# TSOC-ENCORE3.net
KiCad netlist of a schematic drawn in EAGLE
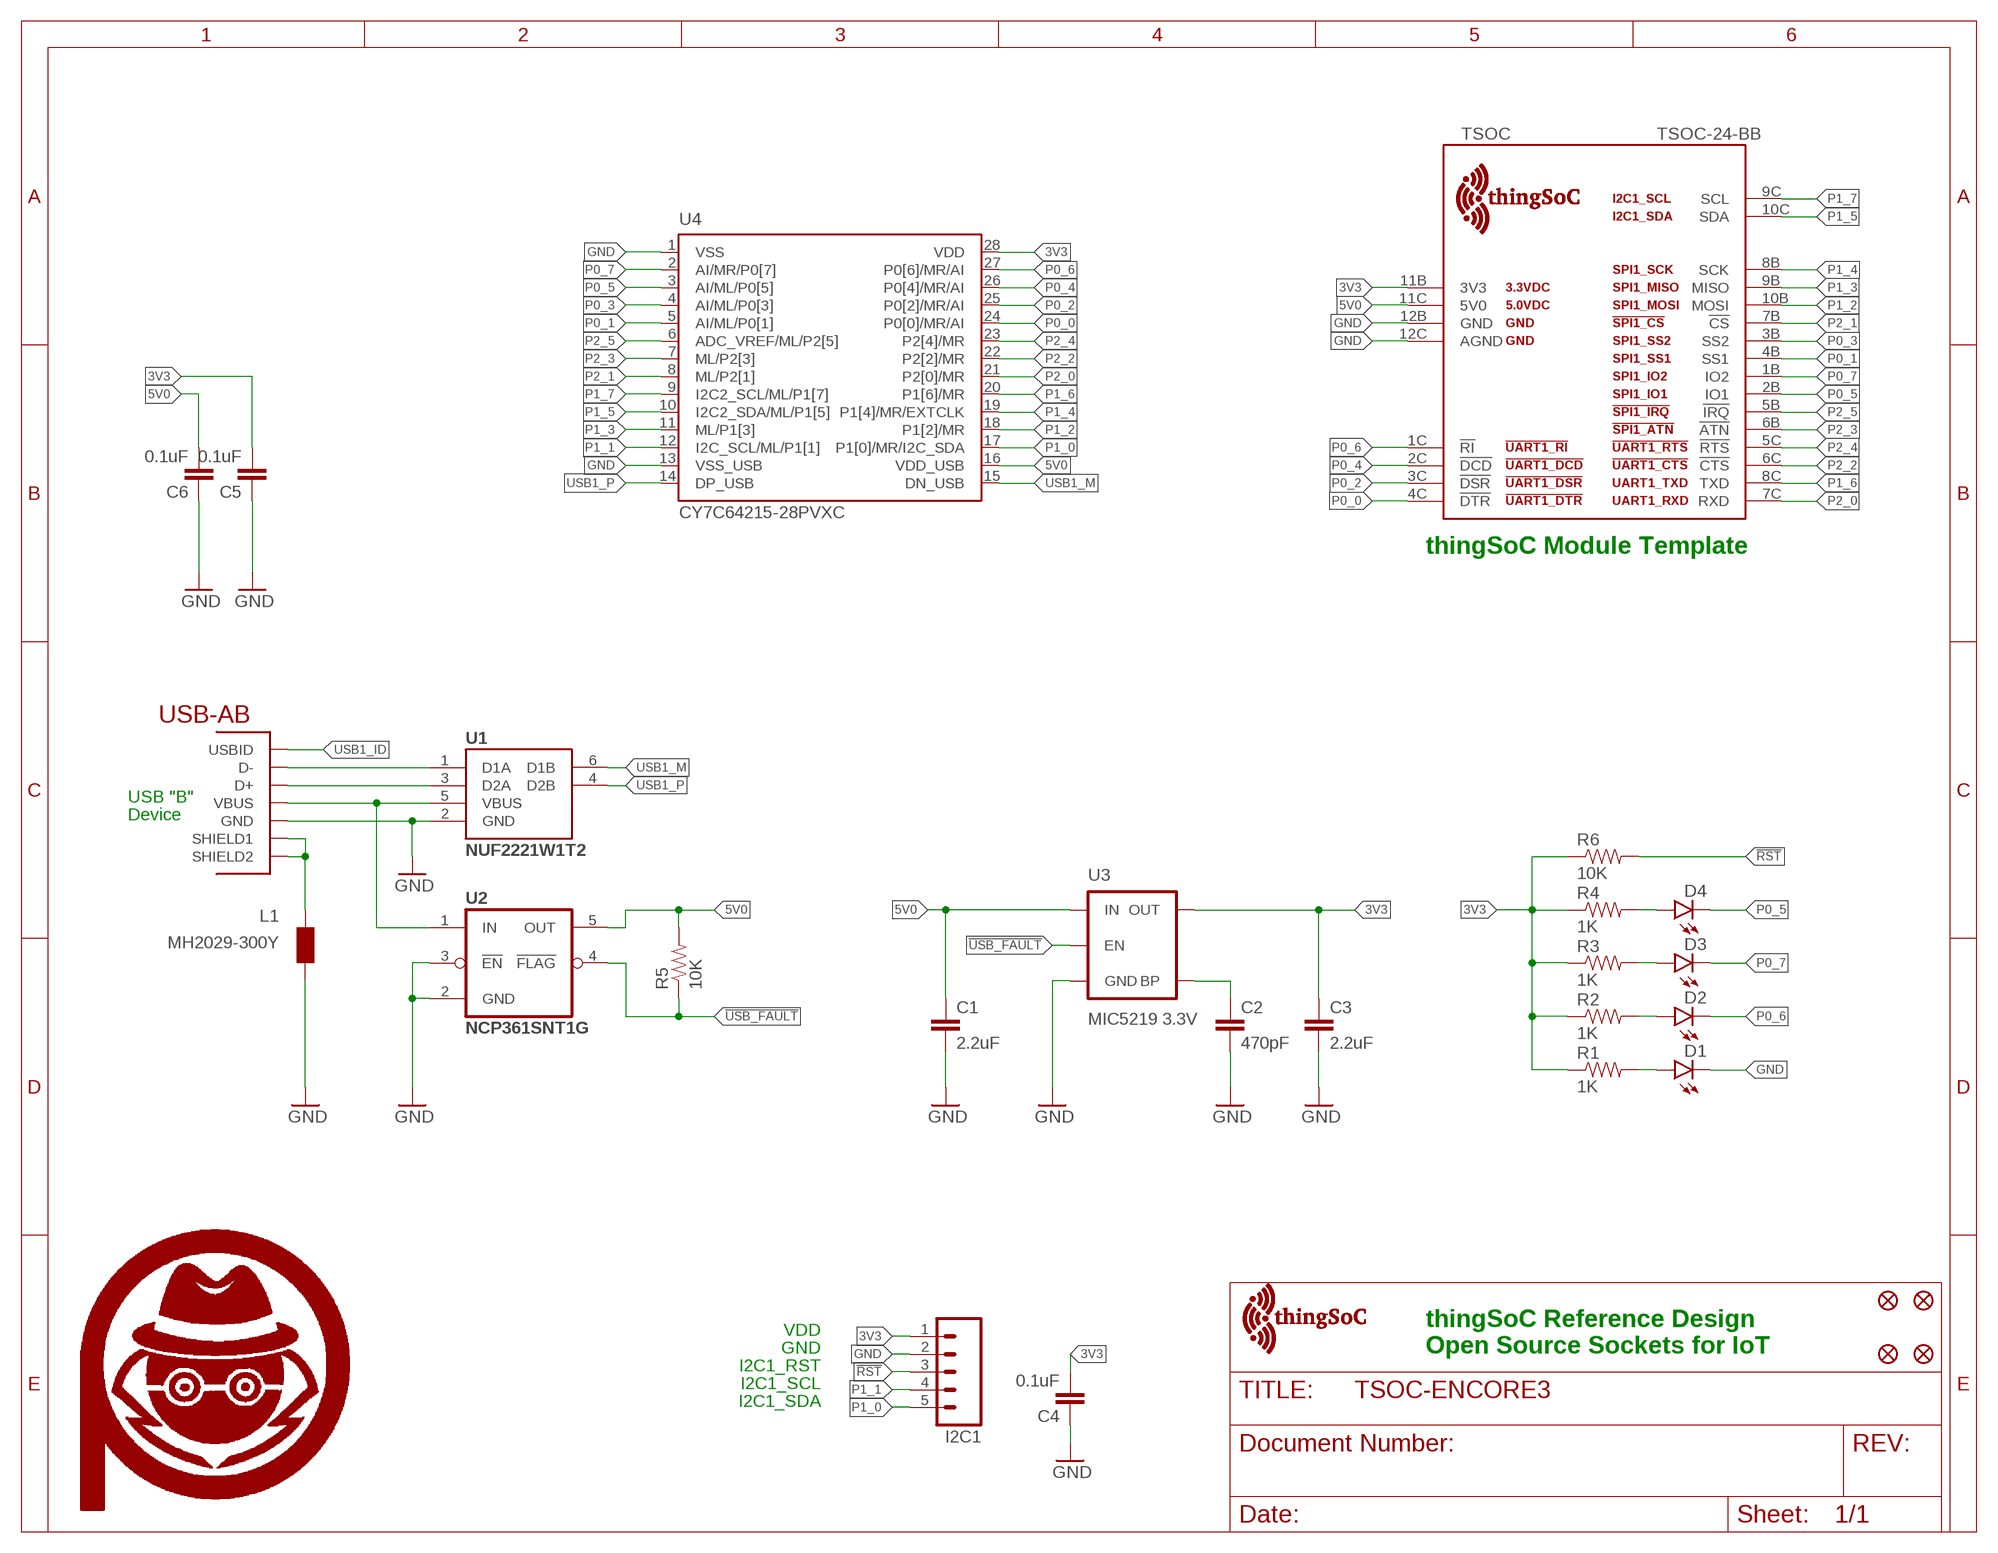
[diagram p0: schematic, sheet 1]

(export (version "E")
  (design (tool "Eeschema 10.0.6"))
  (components
    (comp (ref "C1")
      (value "2.2uF")
      (footprint "eagle-import:0603-CAP")
      (libsource (lib "eagle-import") (part "CAP0603-CAP"))
    )
    (comp (ref "C2")
      (value "470pF")
      (footprint "eagle-import:0603-CAP")
      (libsource (lib "eagle-import") (part "CAP0603-CAP"))
    )
    (comp (ref "C3")
      (value "2.2uF")
      (footprint "eagle-import:0603-CAP")
      (libsource (lib "eagle-import") (part "CAP0603-CAP"))
    )
    (comp (ref "C4")
      (value "0.1uF")
      (footprint "eagle-import:0603-CAP")
      (libsource (lib "eagle-import") (part "CAP0603-CAP"))
    )
    (comp (ref "C5")
      (value "0.1uF")
      (footprint "eagle-import:0603-CAP")
      (libsource (lib "eagle-import") (part "CAP0603-CAP"))
    )
    (comp (ref "C6")
      (value "0.1uF")
      (footprint "eagle-import:0603-CAP")
      (libsource (lib "eagle-import") (part "CAP0603-CAP"))
    )
    (comp (ref "D1")
      (value "LED0603")
      (footprint "eagle-import:LED-0603")
      (libsource (lib "eagle-import") (part "LED0603"))
    )
    (comp (ref "D2")
      (value "LED0603")
      (footprint "eagle-import:LED-0603")
      (libsource (lib "eagle-import") (part "LED0603"))
    )
    (comp (ref "D3")
      (value "LED0603")
      (footprint "eagle-import:LED-0603")
      (libsource (lib "eagle-import") (part "LED0603"))
    )
    (comp (ref "D4")
      (value "LED0603")
      (footprint "eagle-import:LED-0603")
      (libsource (lib "eagle-import") (part "LED0603"))
    )
    (comp (ref "FID1")
      (value "FIDUCIAL1.5X3")
      (footprint "eagle-import:FIDUCIAL-1.5X3")
      (libsource (lib "eagle-import") (part "FIDUCIAL1.5X3"))
    )
    (comp (ref "FID2")
      (value "FIDUCIAL1.5X3")
      (footprint "eagle-import:FIDUCIAL-1.5X3")
      (libsource (lib "eagle-import") (part "FIDUCIAL1.5X3"))
    )
    (comp (ref "FID3")
      (value "FIDUCIAL1.5X3")
      (footprint "eagle-import:FIDUCIAL-1.5X3")
      (libsource (lib "eagle-import") (part "FIDUCIAL1.5X3"))
    )
    (comp (ref "FID4")
      (value "FIDUCIAL1.5X3")
      (footprint "eagle-import:FIDUCIAL-1.5X3")
      (libsource (lib "eagle-import") (part "FIDUCIAL1.5X3"))
    )
    (comp (ref "I2C1")
      (value "M05PTH")
      (footprint "eagle-import:1X05")
      (libsource (lib "eagle-import") (part "M05PTH"))
    )
    (comp (ref "L1")
      (value "MH2029-300Y")
      (footprint "eagle-import:0805")
      (libsource (lib "eagle-import") (part "WE-CBF_0805"))
    )
    (comp (ref "R1")
      (value "1K")
      (footprint "eagle-import:0603-RES")
      (libsource (lib "eagle-import") (part "RESISTOR0603-RES"))
    )
    (comp (ref "R2")
      (value "1K")
      (footprint "eagle-import:0603-RES")
      (libsource (lib "eagle-import") (part "RESISTOR0603-RES"))
    )
    (comp (ref "R3")
      (value "1K")
      (footprint "eagle-import:0603-RES")
      (libsource (lib "eagle-import") (part "RESISTOR0603-RES"))
    )
    (comp (ref "R4")
      (value "1K")
      (footprint "eagle-import:0603-RES")
      (libsource (lib "eagle-import") (part "RESISTOR0603-RES"))
    )
    (comp (ref "R5")
      (value "10K")
      (footprint "eagle-import:0603-RES")
      (libsource (lib "eagle-import") (part "RESISTOR0603-RES"))
    )
    (comp (ref "R6")
      (value "10K")
      (footprint "eagle-import:0603-RES")
      (libsource (lib "eagle-import") (part "RESISTOR0603-RES"))
    )
    (comp (ref "TSOC")
      (value "TSOC-24-BB")
      (footprint "eagle-import:TSOC-BB-S24")
      (libsource (lib "eagle-import") (part "TSOC-24-BB"))
    )
    (comp (ref "U$1")
      (value "PA_LOGO_SYMNULL")
      (footprint "eagle-import:NULL_SYM")
      (libsource (lib "eagle-import") (part "PA_LOGO_SYMNULL"))
    )
    (comp (ref "U$2")
      (value "TSOC-LOGO-MED")
      (footprint "eagle-import:TSOC-LOGO-MED")
      (libsource (lib "eagle-import") (part "TSOC-LOGO-MED"))
    )
    (comp (ref "U$3")
      (value "TSOC-LOGO-MED")
      (footprint "eagle-import:TSOC-LOGO-MED")
      (libsource (lib "eagle-import") (part "TSOC-LOGO-MED"))
    )
    (comp (ref "U1")
      (value "NUF2221W1T2")
      (footprint "eagle-import:SOT-363")
      (libsource (lib "eagle-import") (part "NUF2221W1T2"))
    )
    (comp (ref "U2")
      (value "NCP361SNT1G")
      (footprint "eagle-import:SOP95P275X110-5N")
      (libsource (lib "eagle-import") (part "NCP361SNT1G"))
    )
    (comp (ref "U3")
      (value "MIC5219 3.3V")
      (footprint "eagle-import:SOT23-5")
      (libsource (lib "eagle-import") (part "V_REG_MIC52193.3V"))
    )
    (comp (ref "U4")
      (value "CY7C64215-28PVXC")
      (footprint "eagle-import:SSOP28")
      (libsource (lib "eagle-import") (part "CY7C64215-28PVXC"))
    )
    (comp (ref "USB1")
      (value "USB_AB")
      (footprint "eagle-import:USB-AB-MICRO-SMD")
      (libsource (lib "eagle-import") (part "USB_AB"))
    )
  )
  (nets
    (net (code "1") (name "/~{RST}") (class "Default")
      (node (ref "I2C1") (pin "3") (pinfunction "3_3") (pintype "passive"))
      (node (ref "R6") (pin "2") (pinfunction "2_2") (pintype "passive"))
    )
    (net (code "2") (name "/~{USB_FAULT}") (class "Default")
      (node (ref "R5") (pin "1") (pinfunction "1_1") (pintype "passive"))
      (node (ref "U2") (pin "4") (pinfunction "~{FLAG}_4") (pintype "input"))
      (node (ref "U3") (pin "3") (pinfunction "EN_3") (pintype "input"))
    )
    (net (code "3") (name "3V3") (class "Default")
      (node (ref "C3") (pin "1") (pinfunction "1_1") (pintype "passive"))
      (node (ref "C4") (pin "2") (pinfunction "2_2") (pintype "passive"))
      (node (ref "C5") (pin "2") (pinfunction "2_2") (pintype "passive"))
      (node (ref "I2C1") (pin "1") (pinfunction "1_1") (pintype "passive"))
      (node (ref "R1") (pin "1") (pinfunction "1_1") (pintype "passive"))
      (node (ref "R2") (pin "1") (pinfunction "1_1") (pintype "passive"))
      (node (ref "R3") (pin "1") (pinfunction "1_1") (pintype "passive"))
      (node (ref "R4") (pin "1") (pinfunction "1_1") (pintype "passive"))
      (node (ref "R6") (pin "1") (pinfunction "1_1") (pintype "passive"))
      (node (ref "TSOC") (pin "11B") (pinfunction "3V3_11B") (pintype "bidirectional"))
      (node (ref "U3") (pin "5") (pinfunction "OUT_5") (pintype "passive"))
      (node (ref "U4") (pin "28") (pinfunction "VDD_28") (pintype "power_in"))
    )
    (net (code "4") (name "5V0") (class "Default")
      (node (ref "C1") (pin "1") (pinfunction "1_1") (pintype "passive"))
      (node (ref "C6") (pin "2") (pinfunction "2_2") (pintype "passive"))
      (node (ref "R5") (pin "2") (pinfunction "2_2") (pintype "passive"))
      (node (ref "TSOC") (pin "11C") (pinfunction "5V0_11C") (pintype "bidirectional"))
      (node (ref "U2") (pin "5") (pinfunction "OUT_5") (pintype "output"))
      (node (ref "U3") (pin "1") (pinfunction "IN_1") (pintype "input"))
      (node (ref "U4") (pin "16") (pinfunction "VDD_USB_16") (pintype "power_in"))
    )
    (net (code "5") (name "GND") (class "Default")
      (node (ref "C1") (pin "2") (pinfunction "2_2") (pintype "passive"))
      (node (ref "C2") (pin "2") (pinfunction "2_2") (pintype "passive"))
      (node (ref "C3") (pin "2") (pinfunction "2_2") (pintype "passive"))
      (node (ref "C4") (pin "1") (pinfunction "1_1") (pintype "passive"))
      (node (ref "C5") (pin "1") (pinfunction "1_1") (pintype "passive"))
      (node (ref "C6") (pin "1") (pinfunction "1_1") (pintype "passive"))
      (node (ref "D1") (pin "C") (pinfunction "C_C") (pintype "passive"))
      (node (ref "I2C1") (pin "2") (pinfunction "2_2") (pintype "passive"))
      (node (ref "L1") (pin "2") (pinfunction "2_2") (pintype "passive"))
      (node (ref "TSOC") (pin "12B") (pinfunction "GND_12B") (pintype "bidirectional"))
      (node (ref "TSOC") (pin "12C") (pinfunction "AGND_12C") (pintype "bidirectional"))
      (node (ref "U1") (pin "2") (pinfunction "GND_2") (pintype "bidirectional"))
      (node (ref "U2") (pin "2") (pinfunction "GND_2") (pintype "passive"))
      (node (ref "U2") (pin "3") (pinfunction "~{EN}_3") (pintype "input"))
      (node (ref "U3") (pin "2") (pinfunction "GND_2") (pintype "input"))
      (node (ref "U4") (pin "1") (pinfunction "VSS_1") (pintype "power_in"))
      (node (ref "U4") (pin "13") (pinfunction "VSS_USB_13") (pintype "power_in"))
      (node (ref "USB1") (pin "GND") (pinfunction "GND_GND") (pintype "bidirectional"))
    )
    (net (code "6") (name "Net-(D1-PadA)") (class "Default")
      (node (ref "D1") (pin "A") (pinfunction "A_A") (pintype "passive"))
      (node (ref "R1") (pin "2") (pinfunction "2_2") (pintype "passive"))
    )
    (net (code "7") (name "Net-(D2-PadA)") (class "Default")
      (node (ref "D2") (pin "A") (pinfunction "A_A") (pintype "passive"))
      (node (ref "R2") (pin "2") (pinfunction "2_2") (pintype "passive"))
    )
    (net (code "8") (name "Net-(D3-PadA)") (class "Default")
      (node (ref "D3") (pin "A") (pinfunction "A_A") (pintype "passive"))
      (node (ref "R3") (pin "2") (pinfunction "2_2") (pintype "passive"))
    )
    (net (code "9") (name "Net-(D4-PadA)") (class "Default")
      (node (ref "D4") (pin "A") (pinfunction "A_A") (pintype "passive"))
      (node (ref "R4") (pin "2") (pinfunction "2_2") (pintype "passive"))
    )
    (net (code "10") (name "Net-(L1-Pad1)") (class "Default")
      (node (ref "L1") (pin "1") (pinfunction "1_1") (pintype "passive"))
      (node (ref "USB1") (pin "SHIELD1") (pinfunction "SHIELD1_SHIELD1") (pintype "bidirectional"))
      (node (ref "USB1") (pin "SHIELD2") (pinfunction "SHIELD2_SHIELD2") (pintype "bidirectional"))
    )
    (net (code "11") (name "Net-(U1-D1A)") (class "Default")
      (node (ref "U1") (pin "1") (pinfunction "D1A_1") (pintype "bidirectional"))
      (node (ref "USB1") (pin "D-") (pinfunction "D-_D-") (pintype "bidirectional"))
    )
    (net (code "12") (name "Net-(U1-D2A)") (class "Default")
      (node (ref "U1") (pin "3") (pinfunction "D2A_3") (pintype "bidirectional"))
      (node (ref "USB1") (pin "D+") (pinfunction "D+_D+") (pintype "bidirectional"))
    )
    (net (code "13") (name "Net-(U1-VBUS)") (class "Default")
      (node (ref "U1") (pin "5") (pinfunction "VBUS_5") (pintype "bidirectional"))
      (node (ref "U2") (pin "1") (pinfunction "IN_1") (pintype "power_in"))
      (node (ref "USB1") (pin "VBUS") (pinfunction "VBUS_VBUS") (pintype "bidirectional"))
    )
    (net (code "14") (name "Net-(U3-BP)") (class "Default")
      (node (ref "C2") (pin "1") (pinfunction "1_1") (pintype "passive"))
      (node (ref "U3") (pin "4") (pinfunction "BP_4") (pintype "input"))
    )
    (net (code "15") (name "P0_0") (class "Default")
      (node (ref "TSOC") (pin "4C") (pinfunction "~{DTR}_4C") (pintype "bidirectional"))
      (node (ref "U4") (pin "24") (pinfunction "P0[0]/MR/AI_24") (pintype "bidirectional"))
    )
    (net (code "16") (name "P0_1") (class "Default")
      (node (ref "TSOC") (pin "4B") (pinfunction "SS1_4B") (pintype "bidirectional"))
      (node (ref "U4") (pin "5") (pinfunction "AI/ML/P0[1]_5") (pintype "bidirectional"))
    )
    (net (code "17") (name "P0_2") (class "Default")
      (node (ref "TSOC") (pin "3C") (pinfunction "~{DSR}_3C") (pintype "bidirectional"))
      (node (ref "U4") (pin "25") (pinfunction "P0[2]/MR/AI_25") (pintype "bidirectional"))
    )
    (net (code "18") (name "P0_3") (class "Default")
      (node (ref "TSOC") (pin "3B") (pinfunction "SS2_3B") (pintype "bidirectional"))
      (node (ref "U4") (pin "4") (pinfunction "AI/ML/P0[3]_4") (pintype "bidirectional"))
    )
    (net (code "19") (name "P0_4") (class "Default")
      (node (ref "TSOC") (pin "2C") (pinfunction "~{DCD}_2C") (pintype "bidirectional"))
      (node (ref "U4") (pin "26") (pinfunction "P0[4]/MR/AI_26") (pintype "bidirectional"))
    )
    (net (code "20") (name "P0_5") (class "Default")
      (node (ref "D4") (pin "C") (pinfunction "C_C") (pintype "passive"))
      (node (ref "TSOC") (pin "2B") (pinfunction "IO1_2B") (pintype "bidirectional"))
      (node (ref "U4") (pin "3") (pinfunction "AI/ML/P0[5]_3") (pintype "bidirectional"))
    )
    (net (code "21") (name "P0_6") (class "Default")
      (node (ref "D2") (pin "C") (pinfunction "C_C") (pintype "passive"))
      (node (ref "TSOC") (pin "1C") (pinfunction "~{RI}_1C") (pintype "bidirectional"))
      (node (ref "U4") (pin "27") (pinfunction "P0[6]/MR/AI_27") (pintype "bidirectional"))
    )
    (net (code "22") (name "P0_7") (class "Default")
      (node (ref "D3") (pin "C") (pinfunction "C_C") (pintype "passive"))
      (node (ref "TSOC") (pin "1B") (pinfunction "IO2_1B") (pintype "bidirectional"))
      (node (ref "U4") (pin "2") (pinfunction "AI/MR/P0[7]_2") (pintype "bidirectional"))
    )
    (net (code "23") (name "P1_0") (class "Default")
      (node (ref "I2C1") (pin "5") (pinfunction "5_5") (pintype "passive"))
      (node (ref "U4") (pin "17") (pinfunction "P1[0]/MR/I2C_SDA_17") (pintype "bidirectional"))
    )
    (net (code "24") (name "P1_1") (class "Default")
      (node (ref "I2C1") (pin "4") (pinfunction "4_4") (pintype "passive"))
      (node (ref "U4") (pin "12") (pinfunction "I2C_SCL/ML/P1[1]_12") (pintype "bidirectional"))
    )
    (net (code "25") (name "P1_2") (class "Default")
      (node (ref "TSOC") (pin "10B") (pinfunction "MOSI_10B") (pintype "bidirectional"))
      (node (ref "U4") (pin "18") (pinfunction "P1[2]/MR_18") (pintype "bidirectional"))
    )
    (net (code "26") (name "P1_3") (class "Default")
      (node (ref "TSOC") (pin "9B") (pinfunction "MISO_9B") (pintype "bidirectional"))
      (node (ref "U4") (pin "11") (pinfunction "ML/P1[3]_11") (pintype "bidirectional"))
    )
    (net (code "27") (name "P1_4") (class "Default")
      (node (ref "TSOC") (pin "8B") (pinfunction "SCK_8B") (pintype "bidirectional"))
      (node (ref "U4") (pin "19") (pinfunction "P1[4]/MR/EXTCLK_19") (pintype "bidirectional"))
    )
    (net (code "28") (name "P1_5") (class "Default")
      (node (ref "TSOC") (pin "10C") (pinfunction "SDA_10C") (pintype "bidirectional"))
      (node (ref "U4") (pin "10") (pinfunction "I2C2_SDA/ML/P1[5]_10") (pintype "bidirectional"))
    )
    (net (code "29") (name "P1_6") (class "Default")
      (node (ref "TSOC") (pin "8C") (pinfunction "TXD_8C") (pintype "bidirectional"))
      (node (ref "U4") (pin "20") (pinfunction "P1[6]/MR_20") (pintype "bidirectional"))
    )
    (net (code "30") (name "P1_7") (class "Default")
      (node (ref "TSOC") (pin "9C") (pinfunction "SCL_9C") (pintype "bidirectional"))
      (node (ref "U4") (pin "9") (pinfunction "I2C2_SCL/ML/P1[7]_9") (pintype "bidirectional"))
    )
    (net (code "31") (name "P2_0") (class "Default")
      (node (ref "TSOC") (pin "7C") (pinfunction "RXD_7C") (pintype "bidirectional"))
      (node (ref "U4") (pin "21") (pinfunction "P2[0]/MR_21") (pintype "bidirectional"))
    )
    (net (code "32") (name "P2_1") (class "Default")
      (node (ref "TSOC") (pin "7B") (pinfunction "~{CS}_7B") (pintype "bidirectional"))
      (node (ref "U4") (pin "8") (pinfunction "ML/P2[1]_8") (pintype "bidirectional"))
    )
    (net (code "33") (name "P2_2") (class "Default")
      (node (ref "TSOC") (pin "6C") (pinfunction "~{CTS}_6C") (pintype "bidirectional"))
      (node (ref "U4") (pin "22") (pinfunction "P2[2]/MR_22") (pintype "bidirectional"))
    )
    (net (code "34") (name "P2_3") (class "Default")
      (node (ref "TSOC") (pin "6B") (pinfunction "~{ATN}_6B") (pintype "bidirectional"))
      (node (ref "U4") (pin "7") (pinfunction "ML/P2[3]_7") (pintype "bidirectional"))
    )
    (net (code "35") (name "P2_4") (class "Default")
      (node (ref "TSOC") (pin "5C") (pinfunction "~{RTS}_5C") (pintype "bidirectional"))
      (node (ref "U4") (pin "23") (pinfunction "P2[4]/MR_23") (pintype "bidirectional"))
    )
    (net (code "36") (name "P2_5") (class "Default")
      (node (ref "TSOC") (pin "5B") (pinfunction "~{IRQ}_5B") (pintype "bidirectional"))
      (node (ref "U4") (pin "6") (pinfunction "ADC_VREF/ML/P2[5]_6") (pintype "bidirectional"))
    )
    (net (code "37") (name "USB1_ID") (class "Default")
      (node (ref "USB1") (pin "ID") (pinfunction "USBID_ID") (pintype "bidirectional"))
    )
    (net (code "38") (name "USB1_M") (class "Default")
      (node (ref "U1") (pin "6") (pinfunction "D1B_6") (pintype "bidirectional"))
      (node (ref "U4") (pin "15") (pinfunction "DN_USB_15") (pintype "bidirectional"))
    )
    (net (code "39") (name "USB1_P") (class "Default")
      (node (ref "U1") (pin "4") (pinfunction "D2B_4") (pintype "bidirectional"))
      (node (ref "U4") (pin "14") (pinfunction "DP_USB_14") (pintype "bidirectional"))
    )
  )
)
